# SimpleDuino.net
KiCad netlist of a schematic drawn in EAGLE
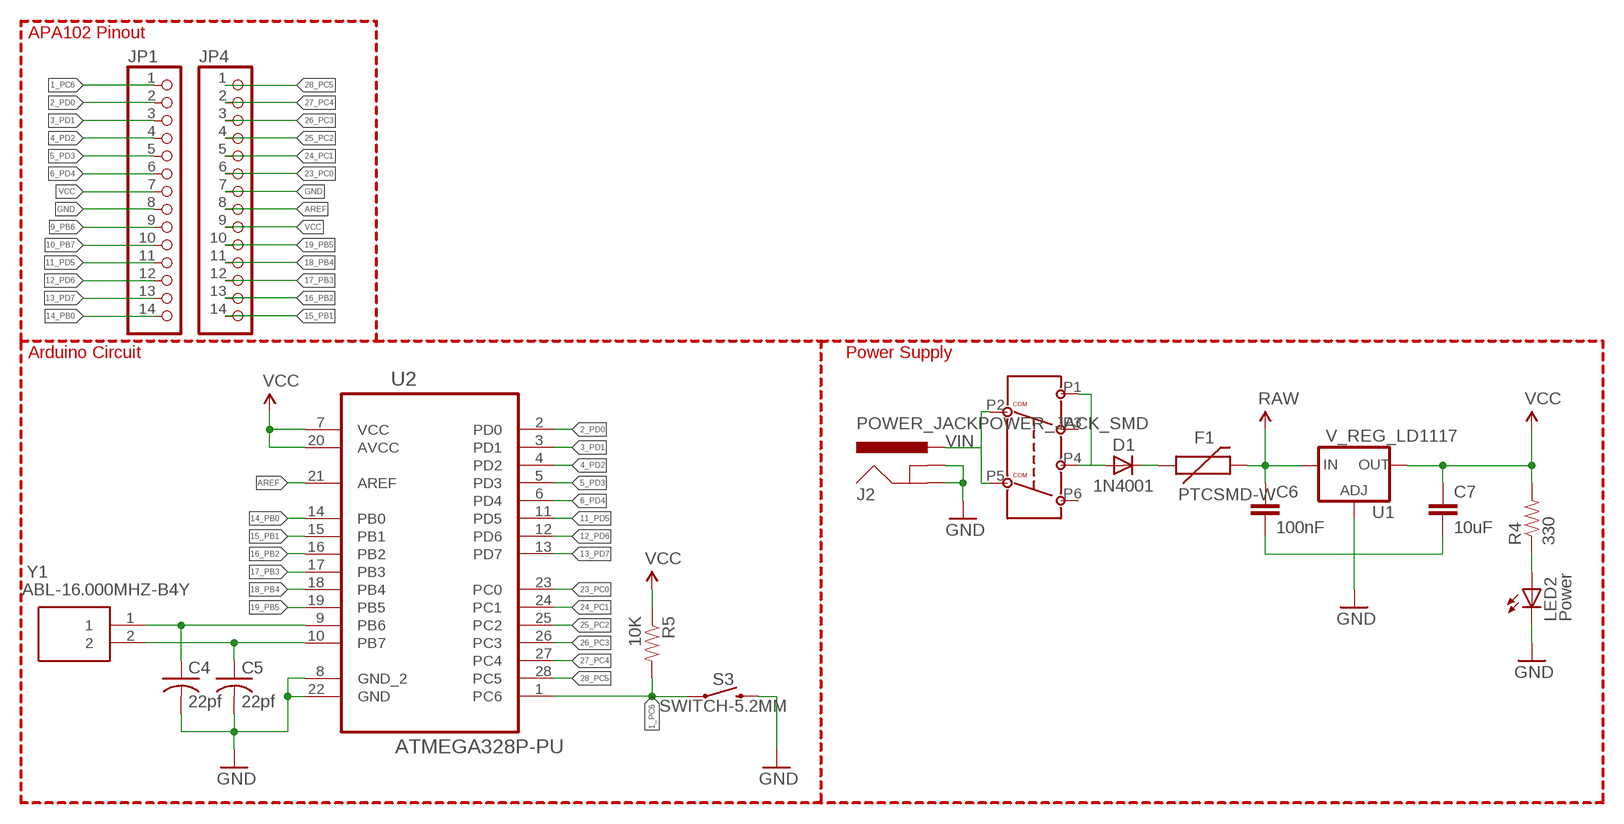
[diagram p0: schematic, sheet 1]

(export (version "E")
  (design (tool "Eeschema 10.0.6"))
  (components
    (comp (ref "C4")
      (value "22pf")
      (footprint "eagle-import:C0805")
      (libsource (lib "eagle-import") (part "C-USC0805"))
    )
    (comp (ref "C5")
      (value "22pf")
      (footprint "eagle-import:C0805")
      (libsource (lib "eagle-import") (part "C-USC0805"))
    )
    (comp (ref "C6")
      (value "100nF")
      (footprint "eagle-import:0603-CAP")
      (libsource (lib "eagle-import") (part "CAP0603-CAP"))
    )
    (comp (ref "C7")
      (value "10uF")
      (footprint "eagle-import:0603-CAP")
      (libsource (lib "eagle-import") (part "CAP0603-CAP"))
    )
    (comp (ref "D1")
      (value "1N4001")
      (footprint "eagle-import:DO41-10")
      (libsource (lib "eagle-import") (part "1N4004"))
    )
    (comp (ref "F1")
      (value "PTCSMD-W")
      (footprint "eagle-import:PTC-1206-WIDE")
      (libsource (lib "eagle-import") (part "PTCSMD-W"))
    )
    (comp (ref "J2")
      (value "POWER_JACKPOWER_JACK_SMD")
      (footprint "eagle-import:POWER_JACK_SMD")
      (libsource (lib "eagle-import") (part "POWER_JACKPOWER_JACK_SMD"))
    )
    (comp (ref "JP1")
      (value "PINHD-1X14")
      (footprint "eagle-import:1X14")
      (libsource (lib "eagle-import") (part "PINHD-1X14"))
    )
    (comp (ref "JP4")
      (value "PINHD-1X14")
      (footprint "eagle-import:1X14")
      (libsource (lib "eagle-import") (part "PINHD-1X14"))
    )
    (comp (ref "LED2")
      (value "Power")
      (footprint "eagle-import:LED-1206")
      (libsource (lib "eagle-import") (part "LED1206"))
    )
    (comp (ref "POWER_SWITCH")
      (value "6-PIN-SLIDE-SWITCH")
      (footprint "eagle-import:6-PIN-SLIDE-SWITCH")
      (libsource (lib "eagle-import") (part "6-PIN-SLIDE-SWITCH"))
    )
    (comp (ref "R4")
      (value "330")
      (footprint "eagle-import:0603-RES")
      (libsource (lib "eagle-import") (part "RESISTOR0603-RES"))
    )
    (comp (ref "R5")
      (value "10K")
      (footprint "eagle-import:0603-RES")
      (libsource (lib "eagle-import") (part "RESISTOR0603-RES"))
    )
    (comp (ref "S3")
      (value "SWITCH-5.2MM")
      (footprint "eagle-import:TACTILE_SWITCH_SMD_5.2MM")
      (libsource (lib "eagle-import") (part "MOMENTARY-SWITCH-SPST-SMD-5.2MM"))
    )
    (comp (ref "U1")
      (value "V_REG_LD1117")
      (footprint "eagle-import:SOT223")
      (libsource (lib "eagle-import") (part "V_REG_317SMD"))
    )
    (comp (ref "U2")
      (value "ATMEGA328P-PU")
      (footprint "eagle-import:DIP254P762X457-28")
      (fields (field (name "MF") "Microchip"))
      (libsource (lib "eagle-import") (part "ATMEGA328P-PU"))
    )
    (comp (ref "Y1")
      (value "ABL-16.000MHZ-B4Y")
      (footprint "eagle-import:HC_49US_(AT49)PTH")
      (fields
        (field (name "MANUFACTURER_PART_NUMBER") "ABL-16.000MHz-B4Y")
        (field (name "MOUSER_PART_NUMBER") "815-ABL-16-B4Y")
      )
      (libsource (lib "eagle-import") (part "ABL-16.000MHZ-B4Y"))
    )
  )
  (nets
    (net (code "1") (name "/VIN") (class "Default")
      (node (ref "J2") (pin "VIN0") (pinfunction "PWR_VIN0") (pintype "bidirectional"))
      (node (ref "POWER_SWITCH") (pin "P2") (pinfunction "2_P2") (pintype "bidirectional"))
      (node (ref "POWER_SWITCH") (pin "P5") (pinfunction "5_P5") (pintype "bidirectional"))
    )
    (net (code "2") (name "1_PC6") (class "Default")
      (node (ref "JP1") (pin "1") (pinfunction "1_1") (pintype "passive"))
      (node (ref "R5") (pin "2") (pinfunction "2_2") (pintype "passive"))
      (node (ref "S3") (pin "1") (pinfunction "1_1") (pintype "passive"))
      (node (ref "U2") (pin "1") (pinfunction "PC6_1") (pintype "bidirectional"))
    )
    (net (code "3") (name "2_PD0") (class "Default")
      (node (ref "JP1") (pin "2") (pinfunction "2_2") (pintype "passive"))
      (node (ref "U2") (pin "2") (pinfunction "PD0_2") (pintype "bidirectional"))
    )
    (net (code "4") (name "3_PD1") (class "Default")
      (node (ref "JP1") (pin "3") (pinfunction "3_3") (pintype "passive"))
      (node (ref "U2") (pin "3") (pinfunction "PD1_3") (pintype "bidirectional"))
    )
    (net (code "5") (name "4_PD2") (class "Default")
      (node (ref "JP1") (pin "4") (pinfunction "4_4") (pintype "passive"))
      (node (ref "U2") (pin "4") (pinfunction "PD2_4") (pintype "bidirectional"))
    )
    (net (code "6") (name "5_PD3") (class "Default")
      (node (ref "JP1") (pin "5") (pinfunction "5_5") (pintype "passive"))
      (node (ref "U2") (pin "5") (pinfunction "PD3_5") (pintype "bidirectional"))
    )
    (net (code "7") (name "6_PD4") (class "Default")
      (node (ref "JP1") (pin "6") (pinfunction "6_6") (pintype "passive"))
      (node (ref "U2") (pin "6") (pinfunction "PD4_6") (pintype "bidirectional"))
    )
    (net (code "8") (name "9_PB6") (class "Default")
      (node (ref "C4") (pin "1") (pinfunction "1_1") (pintype "passive"))
      (node (ref "JP1") (pin "9") (pinfunction "9_9") (pintype "passive"))
      (node (ref "U2") (pin "9") (pinfunction "PB6_9") (pintype "bidirectional"))
      (node (ref "Y1") (pin "1") (pinfunction "1_1") (pintype "bidirectional"))
    )
    (net (code "9") (name "10_PB7") (class "Default")
      (node (ref "C5") (pin "1") (pinfunction "1_1") (pintype "passive"))
      (node (ref "JP1") (pin "10") (pinfunction "10_10") (pintype "passive"))
      (node (ref "U2") (pin "10") (pinfunction "PB7_10") (pintype "bidirectional"))
      (node (ref "Y1") (pin "2") (pinfunction "2_2") (pintype "bidirectional"))
    )
    (net (code "10") (name "11_PD5") (class "Default")
      (node (ref "JP1") (pin "11") (pinfunction "11_11") (pintype "passive"))
      (node (ref "U2") (pin "11") (pinfunction "PD5_11") (pintype "bidirectional"))
    )
    (net (code "11") (name "12_PD6") (class "Default")
      (node (ref "JP1") (pin "12") (pinfunction "12_12") (pintype "passive"))
      (node (ref "U2") (pin "12") (pinfunction "PD6_12") (pintype "bidirectional"))
    )
    (net (code "12") (name "13_PD7") (class "Default")
      (node (ref "JP1") (pin "13") (pinfunction "13_13") (pintype "passive"))
      (node (ref "U2") (pin "13") (pinfunction "PD7_13") (pintype "bidirectional"))
    )
    (net (code "13") (name "14_PB0") (class "Default")
      (node (ref "JP1") (pin "14") (pinfunction "14_14") (pintype "passive"))
      (node (ref "U2") (pin "14") (pinfunction "PB0_14") (pintype "bidirectional"))
    )
    (net (code "14") (name "15_PB1") (class "Default")
      (node (ref "JP4") (pin "14") (pinfunction "14_14") (pintype "passive"))
      (node (ref "U2") (pin "15") (pinfunction "PB1_15") (pintype "bidirectional"))
    )
    (net (code "15") (name "16_PB2") (class "Default")
      (node (ref "JP4") (pin "13") (pinfunction "13_13") (pintype "passive"))
      (node (ref "U2") (pin "16") (pinfunction "PB2_16") (pintype "bidirectional"))
    )
    (net (code "16") (name "17_PB3") (class "Default")
      (node (ref "JP4") (pin "12") (pinfunction "12_12") (pintype "passive"))
      (node (ref "U2") (pin "17") (pinfunction "PB3_17") (pintype "bidirectional"))
    )
    (net (code "17") (name "18_PB4") (class "Default")
      (node (ref "JP4") (pin "11") (pinfunction "11_11") (pintype "passive"))
      (node (ref "U2") (pin "18") (pinfunction "PB4_18") (pintype "bidirectional"))
    )
    (net (code "18") (name "19_PB5") (class "Default")
      (node (ref "JP4") (pin "10") (pinfunction "10_10") (pintype "passive"))
      (node (ref "U2") (pin "19") (pinfunction "PB5_19") (pintype "bidirectional"))
    )
    (net (code "19") (name "23_PC0") (class "Default")
      (node (ref "JP4") (pin "6") (pinfunction "6_6") (pintype "passive"))
      (node (ref "U2") (pin "23") (pinfunction "PC0_23") (pintype "bidirectional"))
    )
    (net (code "20") (name "24_PC1") (class "Default")
      (node (ref "JP4") (pin "5") (pinfunction "5_5") (pintype "passive"))
      (node (ref "U2") (pin "24") (pinfunction "PC1_24") (pintype "bidirectional"))
    )
    (net (code "21") (name "25_PC2") (class "Default")
      (node (ref "JP4") (pin "4") (pinfunction "4_4") (pintype "passive"))
      (node (ref "U2") (pin "25") (pinfunction "PC2_25") (pintype "bidirectional"))
    )
    (net (code "22") (name "26_PC3") (class "Default")
      (node (ref "JP4") (pin "3") (pinfunction "3_3") (pintype "passive"))
      (node (ref "U2") (pin "26") (pinfunction "PC3_26") (pintype "bidirectional"))
    )
    (net (code "23") (name "27_PC4") (class "Default")
      (node (ref "JP4") (pin "2") (pinfunction "2_2") (pintype "passive"))
      (node (ref "U2") (pin "27") (pinfunction "PC4_27") (pintype "bidirectional"))
    )
    (net (code "24") (name "28_PC5") (class "Default")
      (node (ref "JP4") (pin "1") (pinfunction "1_1") (pintype "passive"))
      (node (ref "U2") (pin "28") (pinfunction "PC5_28") (pintype "bidirectional"))
    )
    (net (code "25") (name "AREF") (class "Default")
      (node (ref "JP4") (pin "8") (pinfunction "8_8") (pintype "passive"))
      (node (ref "U2") (pin "21") (pinfunction "AREF_21") (pintype "input"))
    )
    (net (code "26") (name "GND") (class "Default")
      (node (ref "C4") (pin "2") (pinfunction "2_2") (pintype "passive"))
      (node (ref "C5") (pin "2") (pinfunction "2_2") (pintype "passive"))
      (node (ref "C6") (pin "2") (pinfunction "2_2") (pintype "passive"))
      (node (ref "C7") (pin "2") (pinfunction "2_2") (pintype "passive"))
      (node (ref "J2") (pin "GND") (pinfunction "GND_GND") (pintype "bidirectional"))
      (node (ref "J2") (pin "P$4") (pinfunction "GNDBREAK_P$4") (pintype "bidirectional"))
      (node (ref "JP1") (pin "8") (pinfunction "8_8") (pintype "passive"))
      (node (ref "JP4") (pin "7") (pinfunction "7_7") (pintype "passive"))
      (node (ref "LED2") (pin "C") (pinfunction "C_C") (pintype "passive"))
      (node (ref "S3") (pin "3") (pinfunction "2_3") (pintype "passive"))
      (node (ref "U1") (pin "1") (pinfunction "ADJ_1") (pintype "input"))
      (node (ref "U2") (pin "22") (pinfunction "GND_22") (pintype "passive"))
      (node (ref "U2") (pin "8") (pinfunction "GND_2_8") (pintype "passive"))
    )
    (net (code "27") (name "Net-(D1-PadC)") (class "Default")
      (node (ref "D1") (pin "C") (pinfunction "C_C") (pintype "passive"))
      (node (ref "F1") (pin "1") (pinfunction "1_1") (pintype "bidirectional"))
    )
    (net (code "28") (name "Net-(LED2-PadA)") (class "Default")
      (node (ref "LED2") (pin "A") (pinfunction "A_A") (pintype "passive"))
      (node (ref "R4") (pin "1") (pinfunction "1_1") (pintype "passive"))
    )
    (net (code "29") (name "Net-(POWER_SWITCH-1)") (class "Default")
      (node (ref "D1") (pin "A") (pinfunction "A_A") (pintype "passive"))
      (node (ref "POWER_SWITCH") (pin "P1") (pinfunction "1_P1") (pintype "bidirectional"))
      (node (ref "POWER_SWITCH") (pin "P4") (pinfunction "4_P4") (pintype "bidirectional"))
    )
    (net (code "30") (name "RAW") (class "Default")
      (node (ref "C6") (pin "1") (pinfunction "1_1") (pintype "passive"))
      (node (ref "F1") (pin "2") (pinfunction "2_2") (pintype "bidirectional"))
      (node (ref "U1") (pin "3") (pinfunction "IN_3") (pintype "input"))
    )
    (net (code "31") (name "VCC") (class "Default")
      (node (ref "C7") (pin "1") (pinfunction "1_1") (pintype "passive"))
      (node (ref "JP1") (pin "7") (pinfunction "7_7") (pintype "passive"))
      (node (ref "JP4") (pin "9") (pinfunction "9_9") (pintype "passive"))
      (node (ref "R4") (pin "2") (pinfunction "2_2") (pintype "passive"))
      (node (ref "R5") (pin "1") (pinfunction "1_1") (pintype "passive"))
      (node (ref "U1") (pin "2") (pinfunction "OUT_2") (pintype "output"))
      (node (ref "U2") (pin "20") (pinfunction "AVCC_20") (pintype "power_in"))
      (node (ref "U2") (pin "7") (pinfunction "VCC_7") (pintype "power_in"))
    )
    (net (code "32") (name "unconnected-(POWER_SWITCH-3-PadP3)") (class "Default")
      (node (ref "POWER_SWITCH") (pin "P3") (pinfunction "3_P3") (pintype "bidirectional"))
    )
    (net (code "33") (name "unconnected-(POWER_SWITCH-6-PadP6)") (class "Default")
      (node (ref "POWER_SWITCH") (pin "P6") (pinfunction "6_P6") (pintype "bidirectional"))
    )
  )
)
